# schematic.net
KiCad netlist of a schematic drawn in EasyEDA
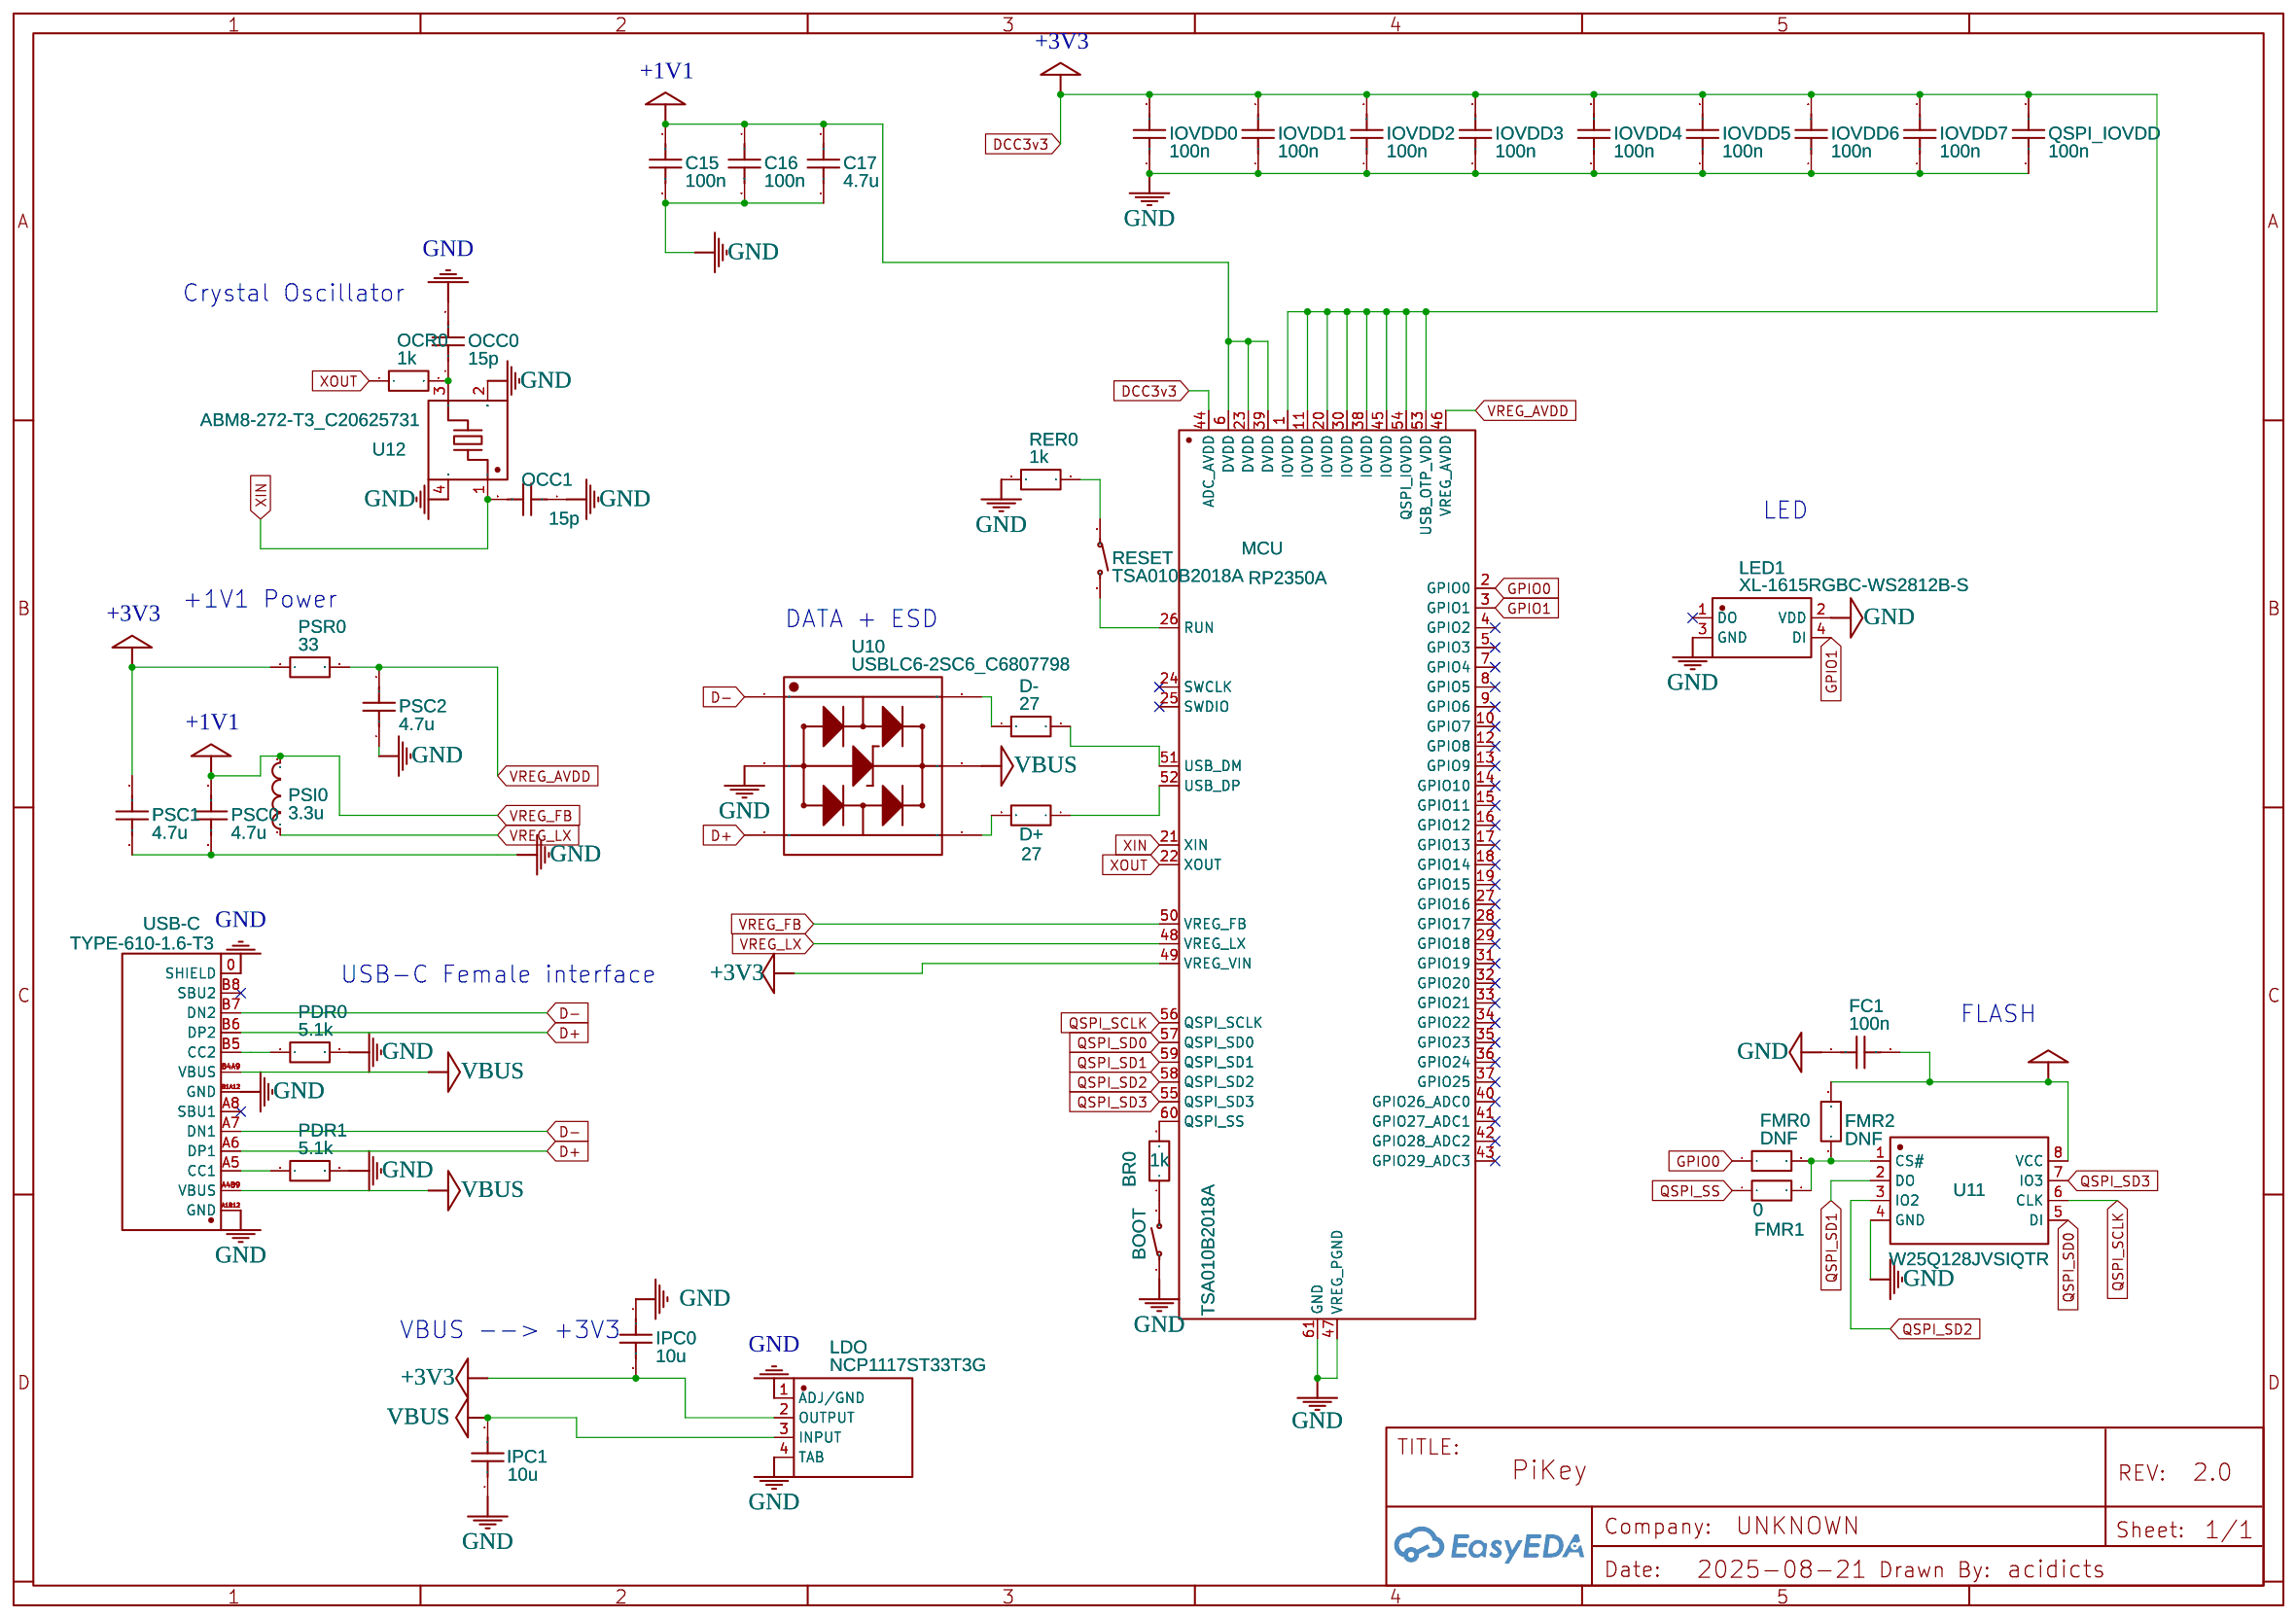
[diagram p0: schematic sheet]

(export (version "E")
  (design (tool "Eeschema 10.0.6"))
  (components
    (comp (ref "BOOT")
      (value "TSA010B2018A")
      (fields (field (name "Manufacturer") "BZCN(博众电气)"))
      (libsource (lib "") (part "TSA010B2018A"))
    )
    (comp (ref "BR0") (value "1k") (libsource (lib "") (part "R_0603_EU_2")))
    (comp (ref "C15") (value "100n") (libsource (lib "") (part "C_0603_US_2")))
    (comp (ref "C16") (value "100n") (libsource (lib "") (part "C_0603_US_2")))
    (comp (ref "C17") (value "4.7u") (libsource (lib "") (part "C_0603_US_2")))
    (comp (ref "D+") (value "27") (libsource (lib "") (part "R_0603_EU")))
    (comp (ref "D-") (value "27") (libsource (lib "") (part "R_0603_EU_5")))
    (comp (ref "FC1") (value "100n") (libsource (lib "") (part "C_0603_US_8")))
    (comp (ref "FMR0") (value "DNF") (libsource (lib "") (part "R_0603_EU_1")))
    (comp (ref "FMR1") (value "0") (libsource (lib "") (part "R_0603_EU_1")))
    (comp (ref "FMR2") (value "DNF") (libsource (lib "") (part "R_0603_EU_3")))
    (comp (ref "IOVDD0") (value "100n") (libsource (lib "") (part "C_0603_US")))
    (comp (ref "IOVDD1") (value "100n") (libsource (lib "") (part "C_0603_US")))
    (comp (ref "IOVDD2") (value "100n") (libsource (lib "") (part "C_0603_US")))
    (comp (ref "IOVDD3") (value "100n") (libsource (lib "") (part "C_0603_US")))
    (comp (ref "IOVDD4") (value "100n") (libsource (lib "") (part "C_0603_US")))
    (comp (ref "IOVDD5") (value "100n") (libsource (lib "") (part "C_0603_US")))
    (comp (ref "IOVDD6") (value "100n") (libsource (lib "") (part "C_0603_US")))
    (comp (ref "IOVDD7") (value "100n") (libsource (lib "") (part "C_0603_US")))
    (comp (ref "IPC0") (value "10u") (libsource (lib "") (part "C_0603_US_4")))
    (comp (ref "IPC1") (value "10u") (libsource (lib "") (part "C_0603_US_7")))
    (comp (ref "LDO")
      (value "NCP1117ST33T3G")
      (fields (field (name "Manufacturer") "onsemi(安森美)"))
      (libsource (lib "") (part "NCP1117ST33T3G"))
    )
    (comp (ref "LED1")
      (value "XL-1615RGBC-WS2812B-S")
      (fields (field (name "Manufacturer") "XINGLIGHT(成兴光)"))
      (libsource (lib "") (part "XL-1615RGBC-WS2812B-S"))
    )
    (comp (ref "MCU") (value "RP2350A") (libsource (lib "") (part "RP2350A")))
    (comp (ref "OCC0") (value "15p") (libsource (lib "") (part "C_0603_US_5")))
    (comp (ref "OCC1") (value "15p") (libsource (lib "") (part "C_0603_US_6")))
    (comp (ref "OCR0") (value "1k") (libsource (lib "") (part "R_0603_EU_7")))
    (comp (ref "PDR0") (value "5.1k") (libsource (lib "") (part "R_0603_EU_6")))
    (comp (ref "PDR1") (value "5.1k") (libsource (lib "") (part "R_0603_EU_6")))
    (comp (ref "PSC0") (value "4.7u") (libsource (lib "") (part "C_0603_US_1")))
    (comp (ref "PSC1") (value "4.7u") (libsource (lib "") (part "C_0603_US_1")))
    (comp (ref "PSC2") (value "4.7u") (libsource (lib "") (part "C_0603_US_1")))
    (comp (ref "PSI0") (value "3.3u") (libsource (lib "") (part "L0603_US")))
    (comp (ref "PSR0") (value "33") (libsource (lib "") (part "R_0603_EU_8")))
    (comp (ref "QSPI_IOVDD") (value "100n") (libsource (lib "") (part "C_0603_US_3")))
    (comp (ref "RER0") (value "1k") (libsource (lib "") (part "R_0603_EU_4")))
    (comp (ref "RESET")
      (value "TSA010B2018A")
      (fields (field (name "Manufacturer") "BZCN(博众电气)"))
      (libsource (lib "") (part "TSA010B2018A_1"))
    )
    (comp (ref "U10")
      (value "USBLC6-2SC6_C6807798")
      (fields
        (field (name "Manufacturer Part") "USBLC6-2SC6")
        (field (name "Manufacturer") "FUXINSEMI(富芯森美)")
      )
      (libsource (lib "") (part "USBLC6-2SC6_C6807798"))
    )
    (comp (ref "U11")
      (value "W25Q128JVSIQTR")
      (fields (field (name "Manufacturer Part") "W25Q128JVSIQ") (field (name "Manufacturer") "Winbond(华邦)"))
      (libsource (lib "") (part "W25Q128JVSIQTR"))
    )
    (comp (ref "U12")
      (value "ABM8-272-T3_C20625731")
      (fields (field (name "Manufacturer Part") "ABM8-272-T3") (field (name "Manufacturer") "ABRACON"))
      (libsource (lib "") (part "ABM8-272-T3_C20625731"))
    )
    (comp (ref "USB-C")
      (value "TYPE-610-1.6-T3")
      (fields (field (name "Manufacturer") "Yuandi(元迪)"))
      (libsource (lib "") (part "TYPE-610-1.6-T3"))
    )
  )
  (nets
    (net (code "1") (name "D+") (class "Default")
      (node (ref "U10") (pin "3") (pinfunction "I/O2_3") (pintype "input"))
      (node (ref "USB-C") (pin "A6") (pinfunction "DP1_A6") (pintype "unspecified"))
      (node (ref "USB-C") (pin "B6") (pinfunction "DP2_B6") (pintype "unspecified"))
    )
    (net (code "2") (name "D-") (class "Default")
      (node (ref "U10") (pin "1") (pinfunction "I/O1_1") (pintype "input"))
      (node (ref "USB-C") (pin "A7") (pinfunction "DN1_A7") (pintype "unspecified"))
      (node (ref "USB-C") (pin "B7") (pinfunction "DN2_B7") (pintype "unspecified"))
    )
    (net (code "3") (name "DCC3v3") (class "Default")
      (node (ref "FC1") (pin "2") (pinfunction "2_2") (pintype "unspecified"))
      (node (ref "FMR2") (pin "2") (pinfunction "2_2") (pintype "unspecified"))
      (node (ref "IOVDD0") (pin "2") (pinfunction "2_2") (pintype "unspecified"))
      (node (ref "IOVDD1") (pin "2") (pinfunction "2_2") (pintype "unspecified"))
      (node (ref "IOVDD2") (pin "2") (pinfunction "2_2") (pintype "unspecified"))
      (node (ref "IOVDD3") (pin "2") (pinfunction "2_2") (pintype "unspecified"))
      (node (ref "IOVDD4") (pin "2") (pinfunction "2_2") (pintype "unspecified"))
      (node (ref "IOVDD5") (pin "2") (pinfunction "2_2") (pintype "unspecified"))
      (node (ref "IOVDD6") (pin "2") (pinfunction "2_2") (pintype "unspecified"))
      (node (ref "IOVDD7") (pin "2") (pinfunction "2_2") (pintype "unspecified"))
      (node (ref "IPC0") (pin "2") (pinfunction "2_2") (pintype "unspecified"))
      (node (ref "LDO") (pin "2") (pinfunction "OUTPUT_2") (pintype "unspecified"))
      (node (ref "MCU") (pin "1") (pinfunction "IOVDD_1") (pintype "unspecified"))
      (node (ref "MCU") (pin "11") (pinfunction "IOVDD_11") (pintype "unspecified"))
      (node (ref "MCU") (pin "20") (pinfunction "IOVDD_20") (pintype "unspecified"))
      (node (ref "MCU") (pin "30") (pinfunction "IOVDD_30") (pintype "unspecified"))
      (node (ref "MCU") (pin "38") (pinfunction "IOVDD_38") (pintype "unspecified"))
      (node (ref "MCU") (pin "44") (pinfunction "ADC_AVDD_44") (pintype "unspecified"))
      (node (ref "MCU") (pin "45") (pinfunction "IOVDD_45") (pintype "unspecified"))
      (node (ref "MCU") (pin "49") (pinfunction "VREG_VIN_49") (pintype "unspecified"))
      (node (ref "MCU") (pin "53") (pinfunction "USB_OTP_VDD_53") (pintype "unspecified"))
      (node (ref "MCU") (pin "54") (pinfunction "QSPI_IOVDD_54") (pintype "unspecified"))
      (node (ref "PSC1") (pin "2") (pinfunction "2_2") (pintype "unspecified"))
      (node (ref "PSR0") (pin "1") (pinfunction "1_1") (pintype "unspecified"))
      (node (ref "QSPI_IOVDD") (pin "2") (pinfunction "2_2") (pintype "unspecified"))
      (node (ref "U11") (pin "8") (pinfunction "VCC_8") (pintype "unspecified"))
    )
    (net (code "4") (name "GND") (class "Default")
      (node (ref "BOOT") (pin "1") (pinfunction "1_1") (pintype "unspecified"))
      (node (ref "C15") (pin "2") (pinfunction "2_2") (pintype "unspecified"))
      (node (ref "C16") (pin "2") (pinfunction "2_2") (pintype "unspecified"))
      (node (ref "C17") (pin "2") (pinfunction "2_2") (pintype "unspecified"))
      (node (ref "FC1") (pin "1") (pinfunction "1_1") (pintype "unspecified"))
      (node (ref "IOVDD0") (pin "1") (pinfunction "1_1") (pintype "unspecified"))
      (node (ref "IOVDD1") (pin "1") (pinfunction "1_1") (pintype "unspecified"))
      (node (ref "IOVDD2") (pin "1") (pinfunction "1_1") (pintype "unspecified"))
      (node (ref "IOVDD3") (pin "1") (pinfunction "1_1") (pintype "unspecified"))
      (node (ref "IOVDD4") (pin "1") (pinfunction "1_1") (pintype "unspecified"))
      (node (ref "IOVDD5") (pin "1") (pinfunction "1_1") (pintype "unspecified"))
      (node (ref "IOVDD6") (pin "1") (pinfunction "1_1") (pintype "unspecified"))
      (node (ref "IOVDD7") (pin "1") (pinfunction "1_1") (pintype "unspecified"))
      (node (ref "IPC0") (pin "1") (pinfunction "1_1") (pintype "unspecified"))
      (node (ref "IPC1") (pin "1") (pinfunction "1_1") (pintype "unspecified"))
      (node (ref "LDO") (pin "1") (pinfunction "ADJ/GND_1") (pintype "unspecified"))
      (node (ref "LDO") (pin "4") (pinfunction "TAB_4") (pintype "unspecified"))
      (node (ref "LED1") (pin "2") (pinfunction "VDD_2") (pintype "unspecified"))
      (node (ref "LED1") (pin "3") (pinfunction "GND_3") (pintype "unspecified"))
      (node (ref "MCU") (pin "47") (pinfunction "VREG_PGND_47") (pintype "unspecified"))
      (node (ref "MCU") (pin "61") (pinfunction "GND_61") (pintype "unspecified"))
      (node (ref "OCC0") (pin "2") (pinfunction "2_2") (pintype "unspecified"))
      (node (ref "OCC1") (pin "1") (pinfunction "1_1") (pintype "unspecified"))
      (node (ref "PDR0") (pin "2") (pinfunction "2_2") (pintype "unspecified"))
      (node (ref "PDR1") (pin "2") (pinfunction "2_2") (pintype "unspecified"))
      (node (ref "PSC0") (pin "1") (pinfunction "1_1") (pintype "unspecified"))
      (node (ref "PSC1") (pin "1") (pinfunction "1_1") (pintype "unspecified"))
      (node (ref "PSC2") (pin "1") (pinfunction "1_1") (pintype "unspecified"))
      (node (ref "QSPI_IOVDD") (pin "1") (pinfunction "1_1") (pintype "unspecified"))
      (node (ref "RER0") (pin "1") (pinfunction "1_1") (pintype "unspecified"))
      (node (ref "U10") (pin "2") (pinfunction "GND_2") (pintype "input"))
      (node (ref "U11") (pin "4") (pinfunction "GND_4") (pintype "unspecified"))
      (node (ref "U12") (pin "2") (pinfunction "GND_2") (pintype "input"))
      (node (ref "U12") (pin "4") (pinfunction "GND_4") (pintype "input"))
      (node (ref "USB-C") (pin "0") (pinfunction "SHIELD_0") (pintype "unspecified"))
      (node (ref "USB-C") (pin "A1B12") (pinfunction "GND_A1B12") (pintype "unspecified"))
      (node (ref "USB-C") (pin "B1A12") (pinfunction "GND_B1A12") (pintype "unspecified"))
    )
    (net (code "5") (name "GPIO0") (class "Default")
      (node (ref "FMR0") (pin "1") (pinfunction "1_1") (pintype "unspecified"))
      (node (ref "MCU") (pin "2") (pinfunction "GPIO0_2") (pintype "unspecified"))
    )
    (net (code "6") (name "GPIO1") (class "Default")
      (node (ref "LED1") (pin "4") (pinfunction "DI_4") (pintype "unspecified"))
      (node (ref "MCU") (pin "3") (pinfunction "GPIO1_3") (pintype "unspecified"))
    )
    (net (code "7") (name "Net-(BOOT-Pad2)") (class "Default")
      (node (ref "BOOT") (pin "2") (pinfunction "2_2") (pintype "unspecified"))
      (node (ref "BR0") (pin "1") (pinfunction "1_1") (pintype "unspecified"))
    )
    (net (code "8") (name "Net-(D+-Pad2)") (class "Default")
      (node (ref "D+") (pin "2") (pinfunction "2_2") (pintype "unspecified"))
      (node (ref "U10") (pin "4") (pinfunction "I/O2_4") (pintype "input"))
    )
    (net (code "9") (name "Net-(D--Pad1)") (class "Default")
      (node (ref "D-") (pin "1") (pinfunction "1_1") (pintype "unspecified"))
      (node (ref "U10") (pin "6") (pinfunction "I/O1_6") (pintype "input"))
    )
    (net (code "10") (name "Net-(MCU-QSPI_SS)") (class "Default")
      (node (ref "BR0") (pin "2") (pinfunction "2_2") (pintype "unspecified"))
      (node (ref "MCU") (pin "60") (pinfunction "QSPI_SS_60") (pintype "unspecified"))
    )
    (net (code "11") (name "Net-(MCU-RUN)") (class "Default")
      (node (ref "MCU") (pin "26") (pinfunction "RUN_26") (pintype "unspecified"))
      (node (ref "RESET") (pin "2") (pinfunction "2_2") (pintype "unspecified"))
    )
    (net (code "12") (name "Net-(MCU-USB_DM)") (class "Default")
      (node (ref "D-") (pin "2") (pinfunction "2_2") (pintype "unspecified"))
      (node (ref "MCU") (pin "51") (pinfunction "USB_DM_51") (pintype "unspecified"))
    )
    (net (code "13") (name "Net-(MCU-USB_DP)") (class "Default")
      (node (ref "D+") (pin "1") (pinfunction "1_1") (pintype "unspecified"))
      (node (ref "MCU") (pin "52") (pinfunction "USB_DP_52") (pintype "unspecified"))
    )
    (net (code "14") (name "Net-(OCC0-Pad1)") (class "Default")
      (node (ref "OCC0") (pin "1") (pinfunction "1_1") (pintype "unspecified"))
      (node (ref "OCR0") (pin "2") (pinfunction "2_2") (pintype "unspecified"))
      (node (ref "U12") (pin "3") (pinfunction "3_3") (pintype "input"))
    )
    (net (code "15") (name "Net-(RER0-Pad2)") (class "Default")
      (node (ref "RER0") (pin "2") (pinfunction "2_2") (pintype "unspecified"))
      (node (ref "RESET") (pin "1") (pinfunction "1_1") (pintype "unspecified"))
    )
    (net (code "16") (name "Net-(U11-CS#)") (class "Default")
      (node (ref "FMR0") (pin "2") (pinfunction "2_2") (pintype "unspecified"))
      (node (ref "FMR1") (pin "2") (pinfunction "2_2") (pintype "unspecified"))
      (node (ref "FMR2") (pin "1") (pinfunction "1_1") (pintype "unspecified"))
      (node (ref "U11") (pin "1") (pinfunction "CS#_1") (pintype "unspecified"))
    )
    (net (code "17") (name "Net-(USB-C-CC1)") (class "Default")
      (node (ref "PDR1") (pin "1") (pinfunction "1_1") (pintype "unspecified"))
      (node (ref "USB-C") (pin "A5") (pinfunction "CC1_A5") (pintype "unspecified"))
    )
    (net (code "18") (name "Net-(USB-C-CC2)") (class "Default")
      (node (ref "PDR0") (pin "1") (pinfunction "1_1") (pintype "unspecified"))
      (node (ref "USB-C") (pin "B5") (pinfunction "CC2_B5") (pintype "unspecified"))
    )
    (net (code "19") (name "QSPI_SCLK") (class "Default")
      (node (ref "MCU") (pin "56") (pinfunction "QSPI_SCLK_56") (pintype "unspecified"))
      (node (ref "U11") (pin "6") (pinfunction "CLK_6") (pintype "unspecified"))
    )
    (net (code "20") (name "QSPI_SD0") (class "Default")
      (node (ref "MCU") (pin "57") (pinfunction "QSPI_SD0_57") (pintype "unspecified"))
      (node (ref "U11") (pin "5") (pinfunction "DI_5") (pintype "unspecified"))
    )
    (net (code "21") (name "QSPI_SD1") (class "Default")
      (node (ref "MCU") (pin "59") (pinfunction "QSPI_SD1_59") (pintype "unspecified"))
      (node (ref "U11") (pin "2") (pinfunction "DO_2") (pintype "unspecified"))
    )
    (net (code "22") (name "QSPI_SD2") (class "Default")
      (node (ref "MCU") (pin "58") (pinfunction "QSPI_SD2_58") (pintype "unspecified"))
      (node (ref "U11") (pin "3") (pinfunction "IO2_3") (pintype "unspecified"))
    )
    (net (code "23") (name "QSPI_SD3") (class "Default")
      (node (ref "MCU") (pin "55") (pinfunction "QSPI_SD3_55") (pintype "unspecified"))
      (node (ref "U11") (pin "7") (pinfunction "IO3_7") (pintype "unspecified"))
    )
    (net (code "24") (name "QSPI_SS") (class "Default")
      (node (ref "FMR1") (pin "1") (pinfunction "1_1") (pintype "unspecified"))
    )
    (net (code "25") (name "VBUS") (class "Default")
      (node (ref "IPC1") (pin "2") (pinfunction "2_2") (pintype "unspecified"))
      (node (ref "LDO") (pin "3") (pinfunction "INPUT_3") (pintype "unspecified"))
      (node (ref "U10") (pin "5") (pinfunction "VCC_5") (pintype "input"))
      (node (ref "USB-C") (pin "A4B9") (pinfunction "VBUS_A4B9") (pintype "unspecified"))
      (node (ref "USB-C") (pin "B4A9") (pinfunction "VBUS_B4A9") (pintype "unspecified"))
    )
    (net (code "26") (name "VREG_AVDD") (class "Default")
      (node (ref "MCU") (pin "46") (pinfunction "VREG_AVDD_46") (pintype "unspecified"))
      (node (ref "PSC2") (pin "2") (pinfunction "2_2") (pintype "unspecified"))
      (node (ref "PSR0") (pin "2") (pinfunction "2_2") (pintype "unspecified"))
    )
    (net (code "27") (name "VREG_FB") (class "Default")
      (node (ref "C15") (pin "1") (pinfunction "1_1") (pintype "unspecified"))
      (node (ref "C16") (pin "1") (pinfunction "1_1") (pintype "unspecified"))
      (node (ref "C17") (pin "1") (pinfunction "1_1") (pintype "unspecified"))
      (node (ref "MCU") (pin "23") (pinfunction "DVDD_23") (pintype "unspecified"))
      (node (ref "MCU") (pin "39") (pinfunction "DVDD_39") (pintype "unspecified"))
      (node (ref "MCU") (pin "50") (pinfunction "VREG_FB_50") (pintype "unspecified"))
      (node (ref "MCU") (pin "6") (pinfunction "DVDD_6") (pintype "unspecified"))
      (node (ref "PSC0") (pin "2") (pinfunction "2_2") (pintype "unspecified"))
      (node (ref "PSI0") (pin "2") (pinfunction "2_2") (pintype "unspecified"))
    )
    (net (code "28") (name "VREG_LX") (class "Default")
      (node (ref "MCU") (pin "48") (pinfunction "VREG_LX_48") (pintype "unspecified"))
      (node (ref "PSI0") (pin "1") (pinfunction "1_1") (pintype "unspecified"))
    )
    (net (code "29") (name "XIN") (class "Default")
      (node (ref "MCU") (pin "21") (pinfunction "XIN_21") (pintype "unspecified"))
      (node (ref "OCC1") (pin "2") (pinfunction "2_2") (pintype "unspecified"))
      (node (ref "U12") (pin "1") (pinfunction "1_1") (pintype "input"))
    )
    (net (code "30") (name "XOUT") (class "Default")
      (node (ref "MCU") (pin "22") (pinfunction "XOUT_22") (pintype "unspecified"))
      (node (ref "OCR0") (pin "1") (pinfunction "1_1") (pintype "unspecified"))
    )
    (net (code "31") (name "unconnected-(LED1-DO-Pad1)") (class "Default")
      (node (ref "LED1") (pin "1") (pinfunction "DO_1") (pintype "unspecified+no_connect"))
    )
    (net (code "32") (name "unconnected-(MCU-GPIO2-Pad4)") (class "Default")
      (node (ref "MCU") (pin "4") (pinfunction "GPIO2_4") (pintype "unspecified+no_connect"))
    )
    (net (code "33") (name "unconnected-(MCU-GPIO3-Pad5)") (class "Default")
      (node (ref "MCU") (pin "5") (pinfunction "GPIO3_5") (pintype "unspecified+no_connect"))
    )
    (net (code "34") (name "unconnected-(MCU-GPIO4-Pad7)") (class "Default")
      (node (ref "MCU") (pin "7") (pinfunction "GPIO4_7") (pintype "unspecified+no_connect"))
    )
    (net (code "35") (name "unconnected-(MCU-GPIO5-Pad8)") (class "Default")
      (node (ref "MCU") (pin "8") (pinfunction "GPIO5_8") (pintype "unspecified+no_connect"))
    )
    (net (code "36") (name "unconnected-(MCU-GPIO6-Pad9)") (class "Default")
      (node (ref "MCU") (pin "9") (pinfunction "GPIO6_9") (pintype "unspecified+no_connect"))
    )
    (net (code "37") (name "unconnected-(MCU-GPIO7-Pad10)") (class "Default")
      (node (ref "MCU") (pin "10") (pinfunction "GPIO7_10") (pintype "unspecified+no_connect"))
    )
    (net (code "38") (name "unconnected-(MCU-GPIO8-Pad12)") (class "Default")
      (node (ref "MCU") (pin "12") (pinfunction "GPIO8_12") (pintype "unspecified+no_connect"))
    )
    (net (code "39") (name "unconnected-(MCU-GPIO9-Pad13)") (class "Default")
      (node (ref "MCU") (pin "13") (pinfunction "GPIO9_13") (pintype "unspecified+no_connect"))
    )
    (net (code "40") (name "unconnected-(MCU-GPIO10-Pad14)") (class "Default")
      (node (ref "MCU") (pin "14") (pinfunction "GPIO10_14") (pintype "unspecified+no_connect"))
    )
    (net (code "41") (name "unconnected-(MCU-GPIO11-Pad15)") (class "Default")
      (node (ref "MCU") (pin "15") (pinfunction "GPIO11_15") (pintype "unspecified+no_connect"))
    )
    (net (code "42") (name "unconnected-(MCU-GPIO12-Pad16)") (class "Default")
      (node (ref "MCU") (pin "16") (pinfunction "GPIO12_16") (pintype "unspecified+no_connect"))
    )
    (net (code "43") (name "unconnected-(MCU-GPIO13-Pad17)") (class "Default")
      (node (ref "MCU") (pin "17") (pinfunction "GPIO13_17") (pintype "unspecified+no_connect"))
    )
    (net (code "44") (name "unconnected-(MCU-GPIO14-Pad18)") (class "Default")
      (node (ref "MCU") (pin "18") (pinfunction "GPIO14_18") (pintype "unspecified+no_connect"))
    )
    (net (code "45") (name "unconnected-(MCU-GPIO15-Pad19)") (class "Default")
      (node (ref "MCU") (pin "19") (pinfunction "GPIO15_19") (pintype "unspecified+no_connect"))
    )
    (net (code "46") (name "unconnected-(MCU-GPIO16-Pad27)") (class "Default")
      (node (ref "MCU") (pin "27") (pinfunction "GPIO16_27") (pintype "unspecified+no_connect"))
    )
    (net (code "47") (name "unconnected-(MCU-GPIO17-Pad28)") (class "Default")
      (node (ref "MCU") (pin "28") (pinfunction "GPIO17_28") (pintype "unspecified+no_connect"))
    )
    (net (code "48") (name "unconnected-(MCU-GPIO18-Pad29)") (class "Default")
      (node (ref "MCU") (pin "29") (pinfunction "GPIO18_29") (pintype "unspecified+no_connect"))
    )
    (net (code "49") (name "unconnected-(MCU-GPIO19-Pad31)") (class "Default")
      (node (ref "MCU") (pin "31") (pinfunction "GPIO19_31") (pintype "unspecified+no_connect"))
    )
    (net (code "50") (name "unconnected-(MCU-GPIO20-Pad32)") (class "Default")
      (node (ref "MCU") (pin "32") (pinfunction "GPIO20_32") (pintype "unspecified+no_connect"))
    )
    (net (code "51") (name "unconnected-(MCU-GPIO21-Pad33)") (class "Default")
      (node (ref "MCU") (pin "33") (pinfunction "GPIO21_33") (pintype "unspecified+no_connect"))
    )
    (net (code "52") (name "unconnected-(MCU-GPIO22-Pad34)") (class "Default")
      (node (ref "MCU") (pin "34") (pinfunction "GPIO22_34") (pintype "unspecified+no_connect"))
    )
    (net (code "53") (name "unconnected-(MCU-GPIO23-Pad35)") (class "Default")
      (node (ref "MCU") (pin "35") (pinfunction "GPIO23_35") (pintype "unspecified+no_connect"))
    )
    (net (code "54") (name "unconnected-(MCU-GPIO24-Pad36)") (class "Default")
      (node (ref "MCU") (pin "36") (pinfunction "GPIO24_36") (pintype "unspecified+no_connect"))
    )
    (net (code "55") (name "unconnected-(MCU-GPIO25-Pad37)") (class "Default")
      (node (ref "MCU") (pin "37") (pinfunction "GPIO25_37") (pintype "unspecified+no_connect"))
    )
    (net (code "56") (name "unconnected-(MCU-GPIO26_ADC0-Pad40)") (class "Default")
      (node (ref "MCU") (pin "40") (pinfunction "GPIO26_ADC0_40") (pintype "unspecified+no_connect"))
    )
    (net (code "57") (name "unconnected-(MCU-GPIO27_ADC1-Pad41)") (class "Default")
      (node (ref "MCU") (pin "41") (pinfunction "GPIO27_ADC1_41") (pintype "unspecified+no_connect"))
    )
    (net (code "58") (name "unconnected-(MCU-GPIO28_ADC2-Pad42)") (class "Default")
      (node (ref "MCU") (pin "42") (pinfunction "GPIO28_ADC2_42") (pintype "unspecified+no_connect"))
    )
    (net (code "59") (name "unconnected-(MCU-GPIO29_ADC3-Pad43)") (class "Default")
      (node (ref "MCU") (pin "43") (pinfunction "GPIO29_ADC3_43") (pintype "unspecified+no_connect"))
    )
    (net (code "60") (name "unconnected-(MCU-SWCLK-Pad24)") (class "Default")
      (node (ref "MCU") (pin "24") (pinfunction "SWCLK_24") (pintype "unspecified+no_connect"))
    )
    (net (code "61") (name "unconnected-(MCU-SWDIO-Pad25)") (class "Default")
      (node (ref "MCU") (pin "25") (pinfunction "SWDIO_25") (pintype "unspecified+no_connect"))
    )
    (net (code "62") (name "unconnected-(USB-C-SBU1-PadA8)") (class "Default")
      (node (ref "USB-C") (pin "A8") (pinfunction "SBU1_A8") (pintype "unspecified+no_connect"))
    )
    (net (code "63") (name "unconnected-(USB-C-SBU2-PadB8)") (class "Default")
      (node (ref "USB-C") (pin "B8") (pinfunction "SBU2_B8") (pintype "unspecified+no_connect"))
    )
  )
)
